# Display18_Cape.net
KiCad netlist of a schematic drawn in EAGLE
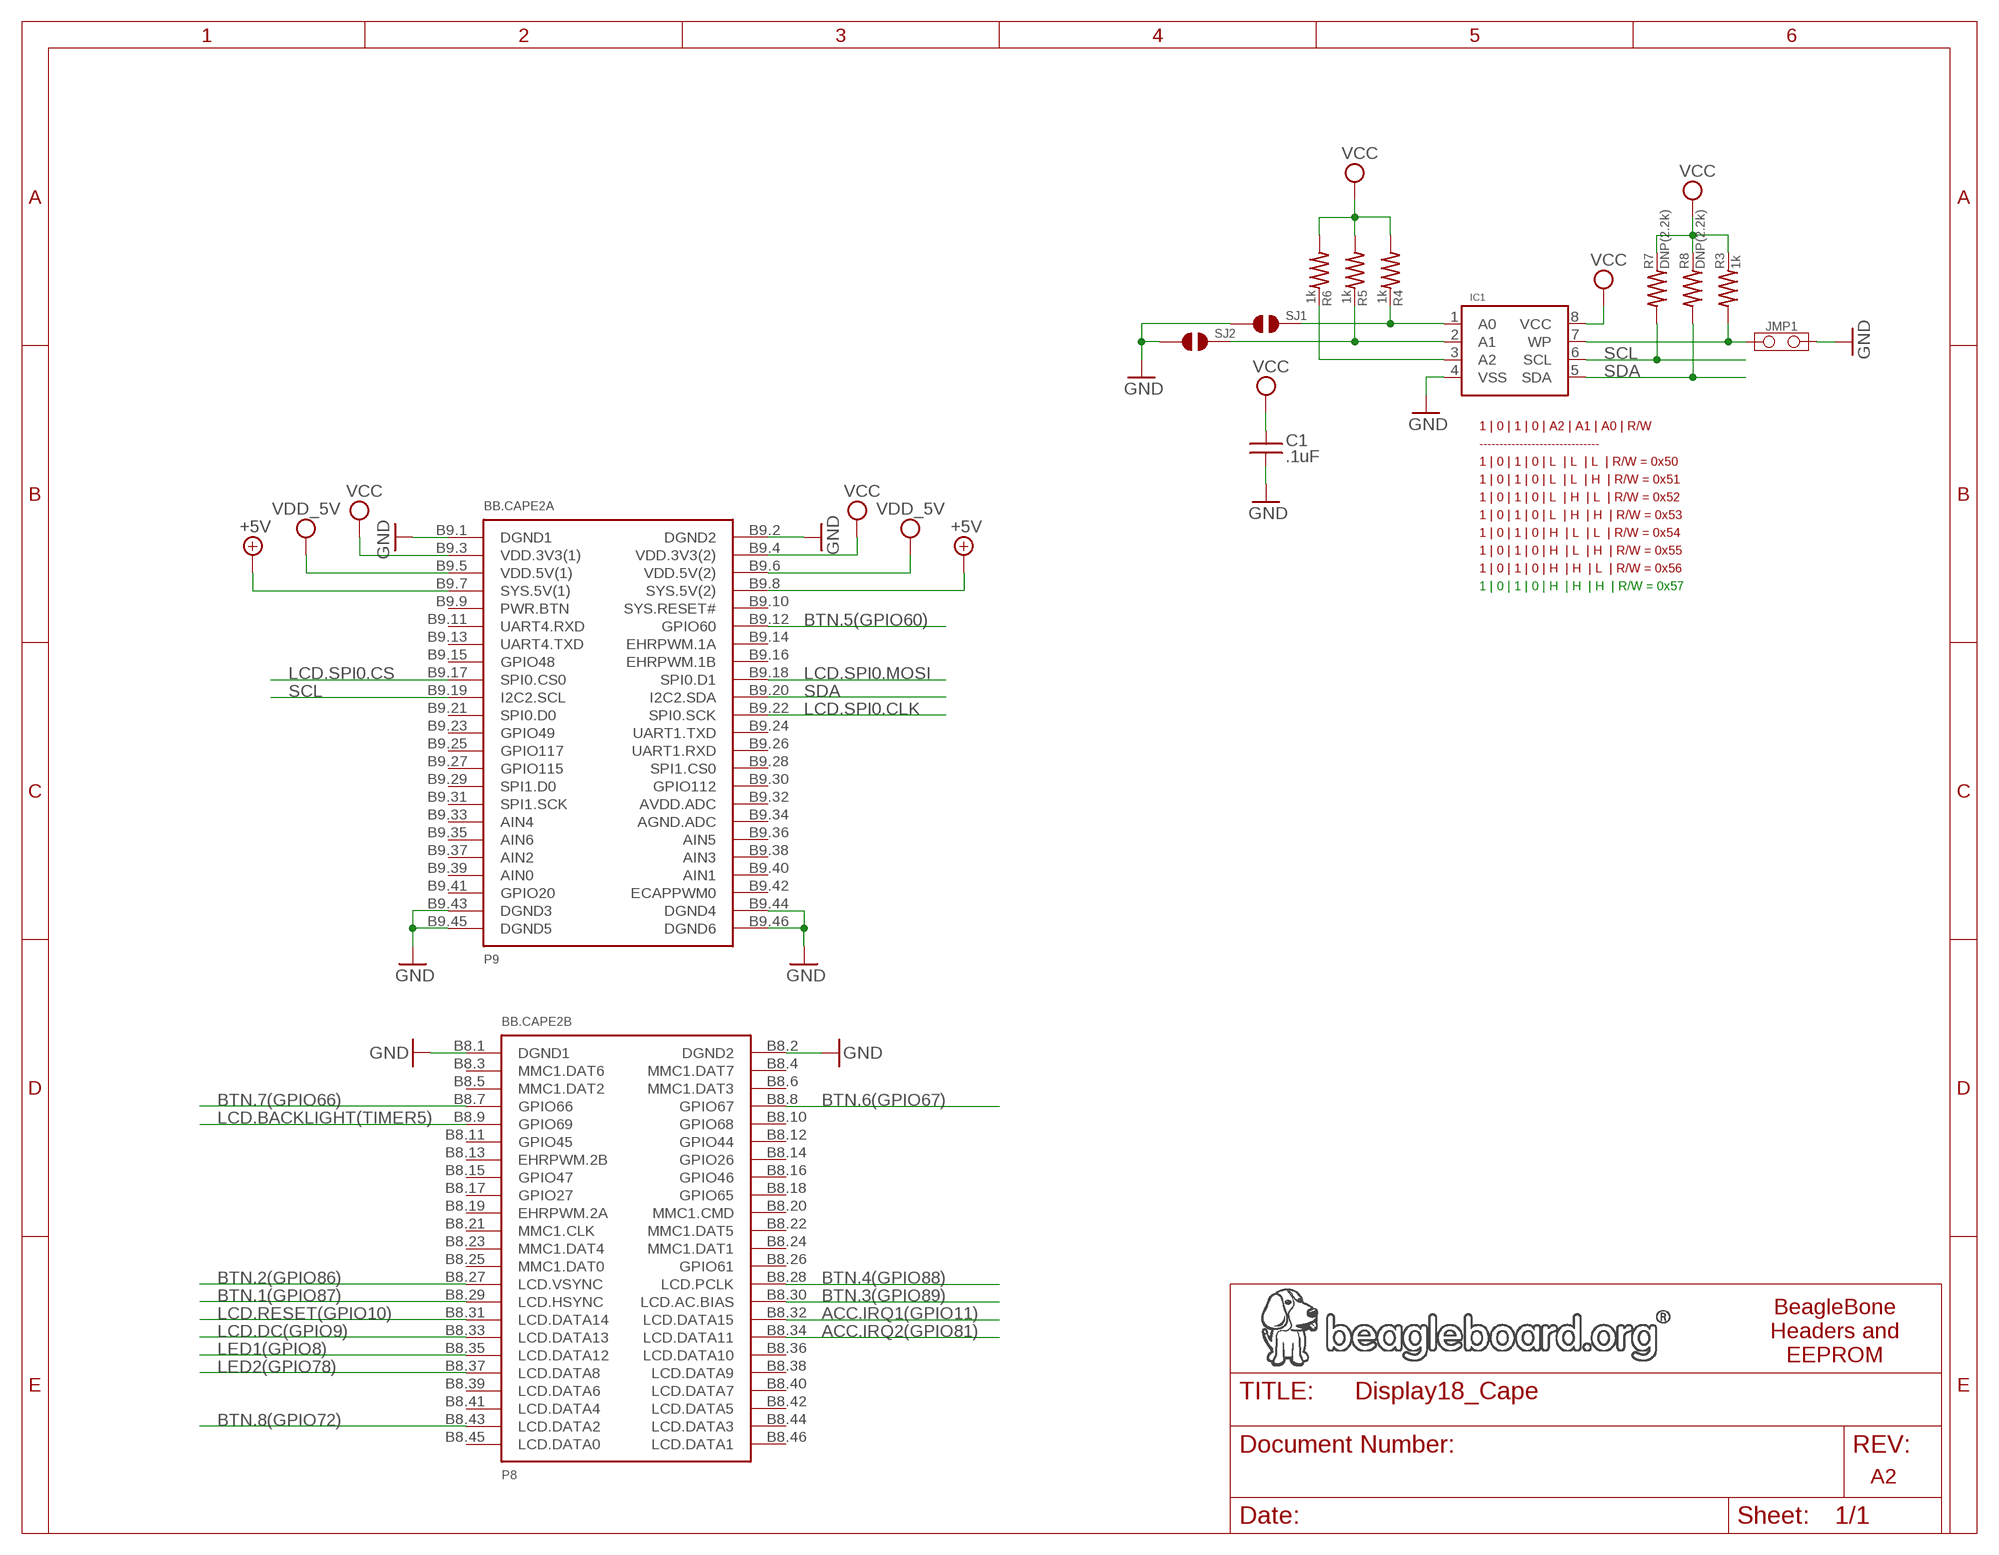
[diagram p0: schematic, sheet 1, part 1 of 2]
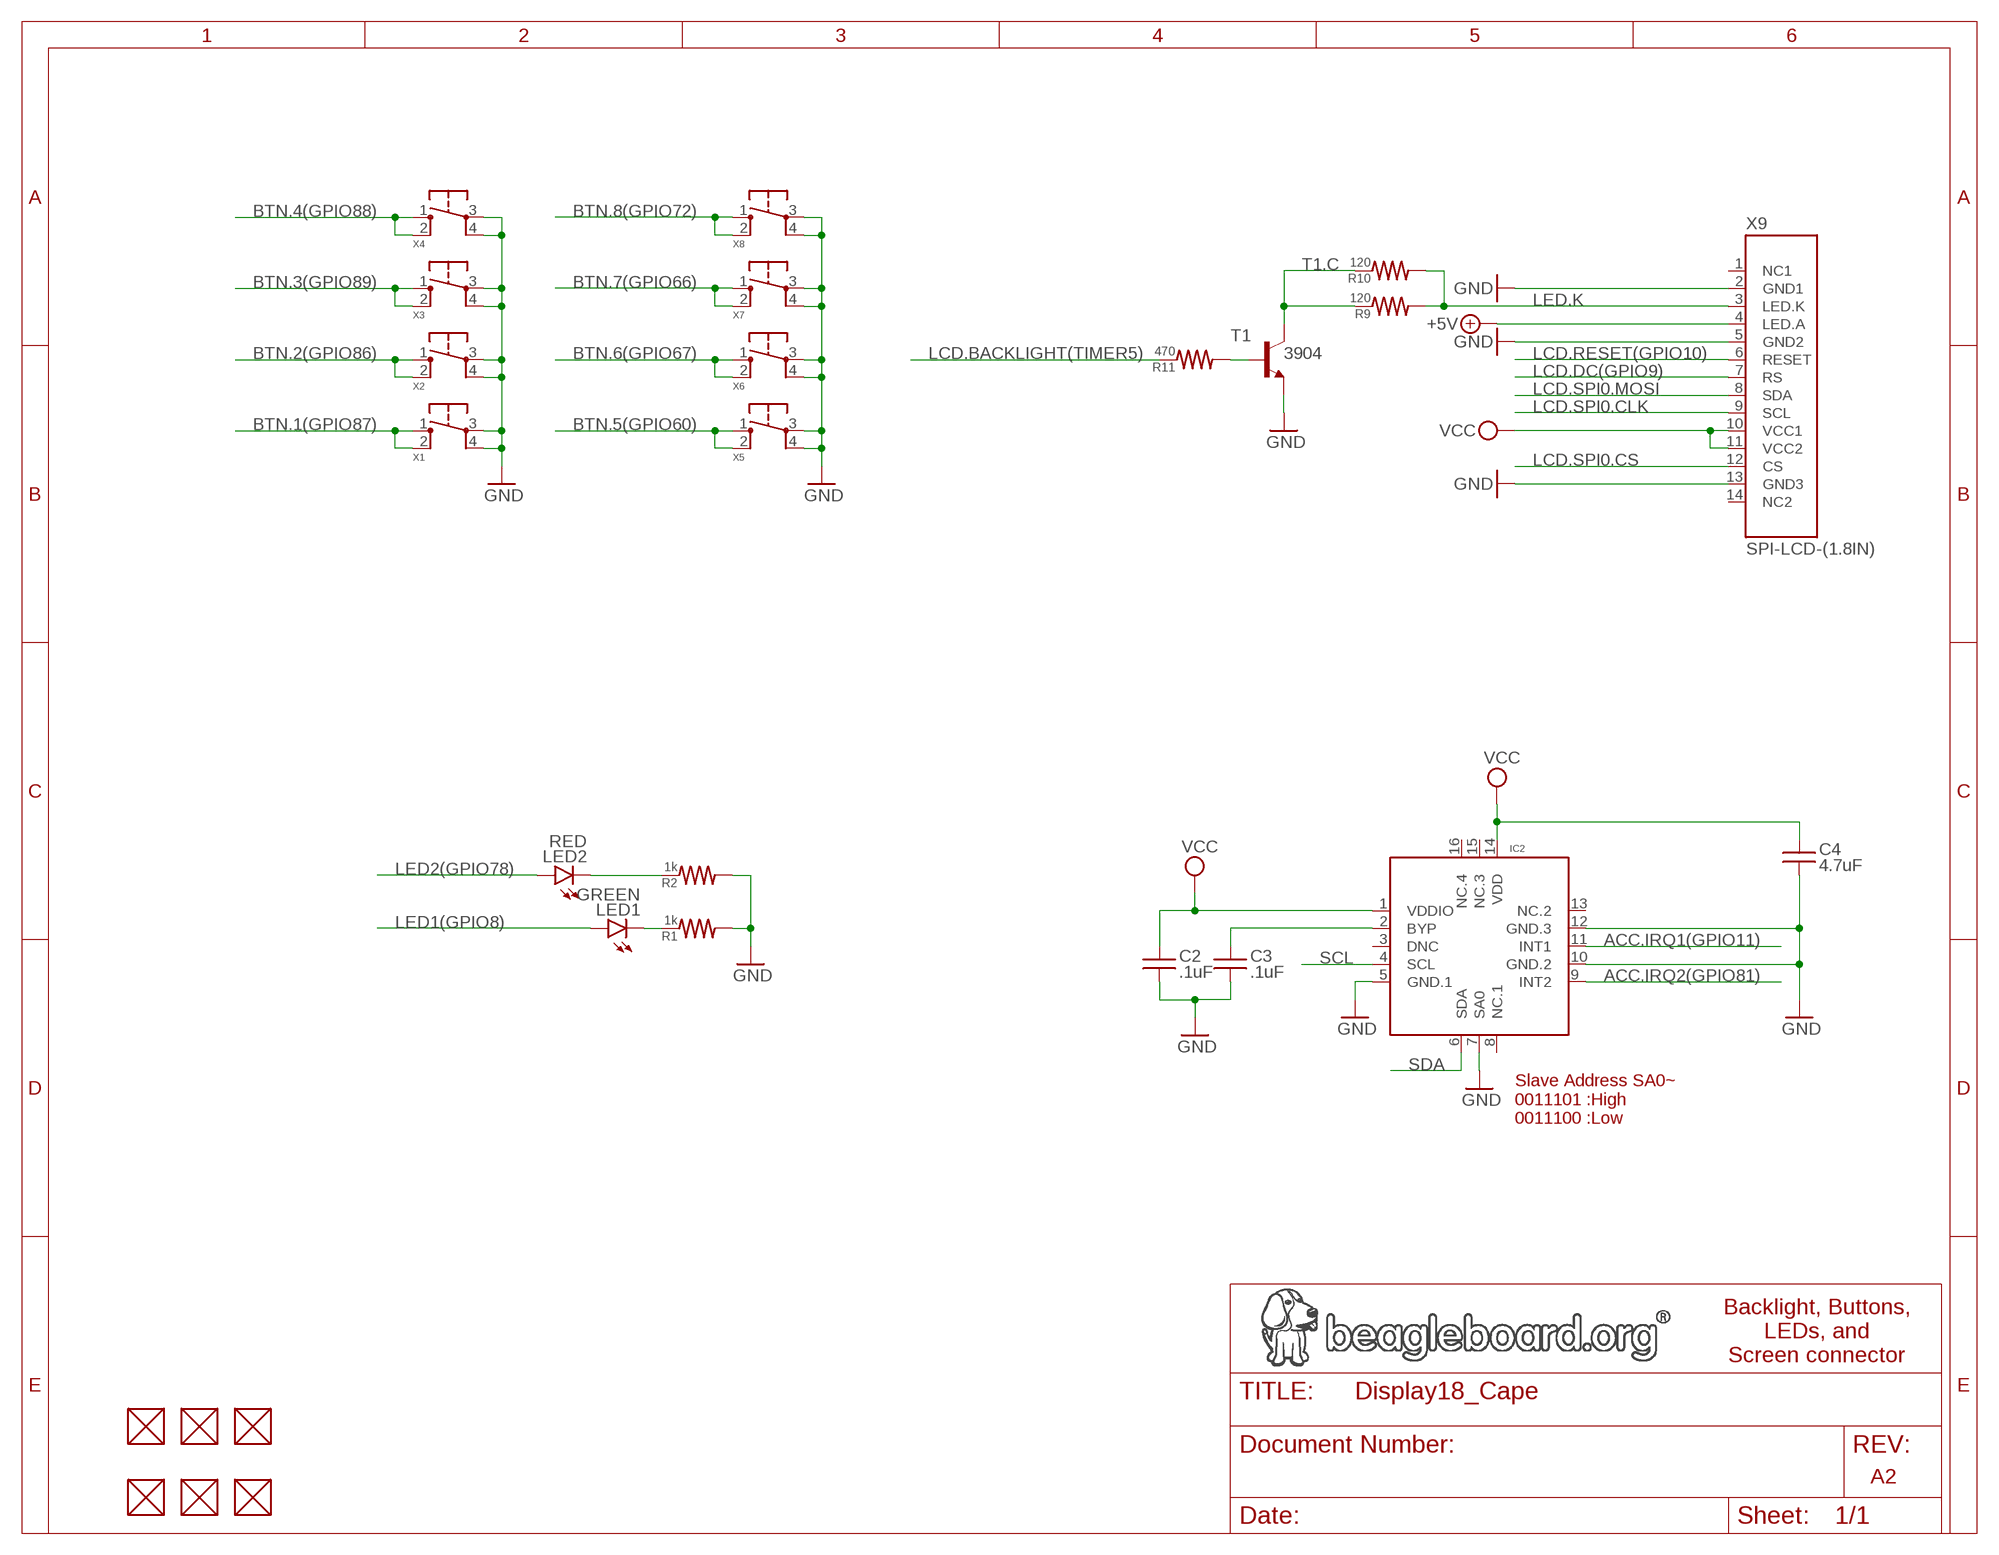
[diagram p1: schematic, sheet 1, part 2 of 2]

(export (version "E")
  (design (tool "Eeschema 10.0.6"))
  (components
    (comp (ref "BB.CAPE2")
      (value "BEAGLEBONE.CAPE.BOTTOM-ONLY-PADS")
      (footprint "eagle-import:BEAGLEBONE.CAPE.BOTTOM-ONLY-PADS")
      (libsource (lib "eagle-import") (part "BEAGLEBONE.CAPE.BOTTOM-ONLY-PADS"))
    )
    (comp (ref "C1")
      (value ".1uF")
      (footprint "eagle-import:0402")
      (libsource (lib "eagle-import") (part "CAPACITOR-(INCH)-0402"))
    )
    (comp (ref "C2")
      (value ".1uF")
      (footprint "eagle-import:0402")
      (libsource (lib "eagle-import") (part "CAPACITOR-(INCH)-0402"))
    )
    (comp (ref "C3")
      (value ".1uF")
      (footprint "eagle-import:0402")
      (libsource (lib "eagle-import") (part "CAPACITOR-(INCH)-0402"))
    )
    (comp (ref "C4")
      (value "4.7uF")
      (footprint "eagle-import:0603")
      (libsource (lib "eagle-import") (part "CAPACITOR-(INCH)-0603"))
    )
    (comp (ref "FUD1")
      (value "FIDUCIAL")
      (footprint "eagle-import:FIDUCIAL_40MIL")
      (libsource (lib "eagle-import") (part "FIDUCIAL"))
    )
    (comp (ref "FUD2")
      (value "FIDUCIAL")
      (footprint "eagle-import:FIDUCIAL_40MIL")
      (libsource (lib "eagle-import") (part "FIDUCIAL"))
    )
    (comp (ref "FUD3")
      (value "FIDUCIAL")
      (footprint "eagle-import:FIDUCIAL_40MIL")
      (libsource (lib "eagle-import") (part "FIDUCIAL"))
    )
    (comp (ref "FUD4")
      (value "FIDUCIAL")
      (footprint "eagle-import:FIDUCIAL_40MIL")
      (libsource (lib "eagle-import") (part "FIDUCIAL"))
    )
    (comp (ref "FUD5")
      (value "FIDUCIAL")
      (footprint "eagle-import:FIDUCIAL_40MIL")
      (libsource (lib "eagle-import") (part "FIDUCIAL"))
    )
    (comp (ref "FUD6")
      (value "FIDUCIAL")
      (footprint "eagle-import:FIDUCIAL_40MIL")
      (libsource (lib "eagle-import") (part "FIDUCIAL"))
    )
    (comp (ref "IC1")
      (value "CAT24C32")
      (footprint "eagle-import:UDFN8,2X3(ON-SEMI)")
      (libsource (lib "eagle-import") (part "CAT24C32"))
    )
    (comp (ref "IC2")
      (value "MMA8453Q")
      (footprint "eagle-import:QFN-16-(MMA8453Q)")
      (libsource (lib "eagle-import") (part "MMA8453Q"))
    )
    (comp (ref "JMP1")
      (value "JUMPER-(X2)")
      (footprint "eagle-import:JUMPER-(X2)")
      (libsource (lib "eagle-import") (part "JUMPER-(X2)"))
    )
    (comp (ref "LED1")
      (value "GREEN")
      (footprint "eagle-import:0805-LED")
      (libsource (lib "eagle-import") (part "LED-(INCH)-0805"))
    )
    (comp (ref "LED2")
      (value "RED")
      (footprint "eagle-import:0805-LED")
      (libsource (lib "eagle-import") (part "LED-(INCH)-0805"))
    )
    (comp (ref "R1")
      (value "1k")
      (footprint "eagle-import:0402")
      (libsource (lib "eagle-import") (part "RESISTOR-(INCH)-0402"))
    )
    (comp (ref "R2")
      (value "1k")
      (footprint "eagle-import:0402")
      (libsource (lib "eagle-import") (part "RESISTOR-(INCH)-0402"))
    )
    (comp (ref "R3")
      (value "1k")
      (footprint "eagle-import:0402")
      (libsource (lib "eagle-import") (part "RESISTOR-(INCH)-0402"))
    )
    (comp (ref "R4")
      (value "1k")
      (footprint "eagle-import:0402")
      (libsource (lib "eagle-import") (part "RESISTOR-(INCH)-0402"))
    )
    (comp (ref "R5")
      (value "1k")
      (footprint "eagle-import:0402")
      (libsource (lib "eagle-import") (part "RESISTOR-(INCH)-0402"))
    )
    (comp (ref "R6")
      (value "1k")
      (footprint "eagle-import:0402")
      (libsource (lib "eagle-import") (part "RESISTOR-(INCH)-0402"))
    )
    (comp (ref "R7")
      (value "DNP(2.2k)")
      (footprint "eagle-import:0402")
      (libsource (lib "eagle-import") (part "RESISTOR-(INCH)-0402"))
    )
    (comp (ref "R8")
      (value "DNP(2.2k)")
      (footprint "eagle-import:0402")
      (libsource (lib "eagle-import") (part "RESISTOR-(INCH)-0402"))
    )
    (comp (ref "R9")
      (value "120")
      (footprint "eagle-import:0603")
      (libsource (lib "eagle-import") (part "RESISTOR-(INCH)-0603"))
    )
    (comp (ref "R10")
      (value "120")
      (footprint "eagle-import:0603")
      (libsource (lib "eagle-import") (part "RESISTOR-(INCH)-0603"))
    )
    (comp (ref "R11")
      (value "470")
      (footprint "eagle-import:0603")
      (libsource (lib "eagle-import") (part "RESISTOR-(INCH)-0603"))
    )
    (comp (ref "SJ1")
      (value "SOLDER.JOINT-(INCH)-0402")
      (footprint "eagle-import:SOLDER.JOINT(0402)")
      (libsource (lib "eagle-import") (part "SOLDER.JOINT-(INCH)-0402"))
    )
    (comp (ref "SJ2")
      (value "SOLDER.JOINT-(INCH)-0402")
      (footprint "eagle-import:SOLDER.JOINT(0402)")
      (libsource (lib "eagle-import") (part "SOLDER.JOINT-(INCH)-0402"))
    )
    (comp (ref "T1")
      (value "3904")
      (footprint "eagle-import:SOT23-BEC")
      (libsource (lib "eagle-import") (part "-NPN-SOT23-BECBC847"))
    )
    (comp (ref "X1")
      (value "6MM_TACTILE_SWITCH")
      (footprint "eagle-import:6MM_TACTILE-SWITCH")
      (libsource (lib "eagle-import") (part "6MM_TACTILE_SWITCH"))
    )
    (comp (ref "X2")
      (value "6MM_TACTILE_SWITCH")
      (footprint "eagle-import:6MM_TACTILE-SWITCH")
      (libsource (lib "eagle-import") (part "6MM_TACTILE_SWITCH"))
    )
    (comp (ref "X3")
      (value "6MM_TACTILE_SWITCH")
      (footprint "eagle-import:6MM_TACTILE-SWITCH")
      (libsource (lib "eagle-import") (part "6MM_TACTILE_SWITCH"))
    )
    (comp (ref "X4")
      (value "6MM_TACTILE_SWITCH")
      (footprint "eagle-import:6MM_TACTILE-SWITCH")
      (libsource (lib "eagle-import") (part "6MM_TACTILE_SWITCH"))
    )
    (comp (ref "X5")
      (value "6MM_TACTILE_SWITCH")
      (footprint "eagle-import:6MM_TACTILE-SWITCH")
      (libsource (lib "eagle-import") (part "6MM_TACTILE_SWITCH"))
    )
    (comp (ref "X6")
      (value "6MM_TACTILE_SWITCH")
      (footprint "eagle-import:6MM_TACTILE-SWITCH")
      (libsource (lib "eagle-import") (part "6MM_TACTILE_SWITCH"))
    )
    (comp (ref "X7")
      (value "6MM_TACTILE_SWITCH")
      (footprint "eagle-import:6MM_TACTILE-SWITCH")
      (libsource (lib "eagle-import") (part "6MM_TACTILE_SWITCH"))
    )
    (comp (ref "X8")
      (value "6MM_TACTILE_SWITCH")
      (footprint "eagle-import:6MM_TACTILE-SWITCH")
      (libsource (lib "eagle-import") (part "6MM_TACTILE_SWITCH"))
    )
    (comp (ref "X9")
      (value "SPI-LCD-(1.8IN)")
      (footprint "eagle-import:LCD-(1.8IN)")
      (libsource (lib "eagle-import") (part "SPI-LCD-(1.8IN)"))
    )
  )
  (nets
    (net (code "1") (name "+5V") (class "Default")
      (node (ref "BB.CAPE2") (pin "B9.7") (pinfunction "SYS.5V(1)_B9.7") (pintype "bidirectional"))
      (node (ref "BB.CAPE2") (pin "B9.8") (pinfunction "SYS.5V(2)_B9.8") (pintype "bidirectional"))
      (node (ref "X9") (pin "4") (pinfunction "LED.A_4") (pintype "bidirectional"))
    )
    (net (code "2") (name "/ACC.IRQ1(GPIO11)") (class "Default")
      (node (ref "BB.CAPE2") (pin "B8.32") (pinfunction "LCD.DATA15_B8.32") (pintype "bidirectional"))
      (node (ref "IC2") (pin "11") (pinfunction "INT1_11") (pintype "bidirectional"))
    )
    (net (code "3") (name "/ACC.IRQ2(GPIO81)") (class "Default")
      (node (ref "BB.CAPE2") (pin "B8.34") (pinfunction "LCD.DATA11_B8.34") (pintype "bidirectional"))
      (node (ref "IC2") (pin "9") (pinfunction "INT2_9") (pintype "bidirectional"))
    )
    (net (code "4") (name "/BTN.1(GPIO87)") (class "Default")
      (node (ref "BB.CAPE2") (pin "B8.29") (pinfunction "LCD.HSYNC_B8.29") (pintype "bidirectional"))
      (node (ref "X1") (pin "1") (pinfunction "1_1") (pintype "bidirectional"))
      (node (ref "X1") (pin "2") (pinfunction "2_2") (pintype "bidirectional"))
    )
    (net (code "5") (name "/BTN.2(GPIO86)") (class "Default")
      (node (ref "BB.CAPE2") (pin "B8.27") (pinfunction "LCD.VSYNC_B8.27") (pintype "bidirectional"))
      (node (ref "X2") (pin "1") (pinfunction "1_1") (pintype "bidirectional"))
      (node (ref "X2") (pin "2") (pinfunction "2_2") (pintype "bidirectional"))
    )
    (net (code "6") (name "/BTN.3(GPIO89)") (class "Default")
      (node (ref "BB.CAPE2") (pin "B8.30") (pinfunction "LCD.AC.BIAS_B8.30") (pintype "bidirectional"))
      (node (ref "X3") (pin "1") (pinfunction "1_1") (pintype "bidirectional"))
      (node (ref "X3") (pin "2") (pinfunction "2_2") (pintype "bidirectional"))
    )
    (net (code "7") (name "/BTN.4(GPIO88)") (class "Default")
      (node (ref "BB.CAPE2") (pin "B8.28") (pinfunction "LCD.PCLK_B8.28") (pintype "bidirectional"))
      (node (ref "X4") (pin "1") (pinfunction "1_1") (pintype "bidirectional"))
      (node (ref "X4") (pin "2") (pinfunction "2_2") (pintype "bidirectional"))
    )
    (net (code "8") (name "/BTN.5(GPIO60)") (class "Default")
      (node (ref "BB.CAPE2") (pin "B9.12") (pinfunction "GPIO60_B9.12") (pintype "bidirectional"))
      (node (ref "X5") (pin "1") (pinfunction "1_1") (pintype "bidirectional"))
      (node (ref "X5") (pin "2") (pinfunction "2_2") (pintype "bidirectional"))
    )
    (net (code "9") (name "/BTN.6(GPIO67)") (class "Default")
      (node (ref "BB.CAPE2") (pin "B8.8") (pinfunction "GPIO67_B8.8") (pintype "bidirectional"))
      (node (ref "X6") (pin "1") (pinfunction "1_1") (pintype "bidirectional"))
      (node (ref "X6") (pin "2") (pinfunction "2_2") (pintype "bidirectional"))
    )
    (net (code "10") (name "/BTN.7(GPIO66)") (class "Default")
      (node (ref "BB.CAPE2") (pin "B8.7") (pinfunction "GPIO66_B8.7") (pintype "bidirectional"))
      (node (ref "X7") (pin "1") (pinfunction "1_1") (pintype "bidirectional"))
      (node (ref "X7") (pin "2") (pinfunction "2_2") (pintype "bidirectional"))
    )
    (net (code "11") (name "/BTN.8(GPIO72)") (class "Default")
      (node (ref "BB.CAPE2") (pin "B8.43") (pinfunction "LCD.DATA2_B8.43") (pintype "bidirectional"))
      (node (ref "X8") (pin "1") (pinfunction "1_1") (pintype "bidirectional"))
      (node (ref "X8") (pin "2") (pinfunction "2_2") (pintype "bidirectional"))
    )
    (net (code "12") (name "/LCD.BACKLIGHT(TIMER5)") (class "Default")
      (node (ref "BB.CAPE2") (pin "B8.9") (pinfunction "GPIO69_B8.9") (pintype "bidirectional"))
      (node (ref "R11") (pin "2") (pinfunction "2_2") (pintype "bidirectional"))
    )
    (net (code "13") (name "/LCD.DC(GPIO9)") (class "Default")
      (node (ref "BB.CAPE2") (pin "B8.33") (pinfunction "LCD.DATA13_B8.33") (pintype "bidirectional"))
      (node (ref "X9") (pin "7") (pinfunction "RS_7") (pintype "bidirectional"))
    )
    (net (code "14") (name "/LCD.RESET(GPIO10)") (class "Default")
      (node (ref "BB.CAPE2") (pin "B8.31") (pinfunction "LCD.DATA14_B8.31") (pintype "bidirectional"))
      (node (ref "X9") (pin "6") (pinfunction "RESET_6") (pintype "bidirectional"))
    )
    (net (code "15") (name "/LCD.SPI0.CLK") (class "Default")
      (node (ref "BB.CAPE2") (pin "B9.22") (pinfunction "SPI0.SCK_B9.22") (pintype "bidirectional"))
      (node (ref "X9") (pin "9") (pinfunction "SCL_9") (pintype "bidirectional"))
    )
    (net (code "16") (name "/LCD.SPI0.CS") (class "Default")
      (node (ref "BB.CAPE2") (pin "B9.17") (pinfunction "SPI0.CS0_B9.17") (pintype "bidirectional"))
      (node (ref "X9") (pin "12") (pinfunction "CS_12") (pintype "bidirectional"))
    )
    (net (code "17") (name "/LCD.SPI0.MOSI") (class "Default")
      (node (ref "BB.CAPE2") (pin "B9.18") (pinfunction "SPI0.D1_B9.18") (pintype "bidirectional"))
      (node (ref "X9") (pin "8") (pinfunction "SDA_8") (pintype "bidirectional"))
    )
    (net (code "18") (name "/LED.K") (class "Default")
      (node (ref "R10") (pin "1") (pinfunction "1_1") (pintype "bidirectional"))
      (node (ref "R9") (pin "1") (pinfunction "1_1") (pintype "bidirectional"))
      (node (ref "X9") (pin "3") (pinfunction "LED.K_3") (pintype "bidirectional"))
    )
    (net (code "19") (name "/LED1(GPIO8)") (class "Default")
      (node (ref "BB.CAPE2") (pin "B8.35") (pinfunction "LCD.DATA12_B8.35") (pintype "bidirectional"))
      (node (ref "LED1") (pin "A") (pinfunction "A_A") (pintype "passive"))
    )
    (net (code "20") (name "/LED2(GPIO78)") (class "Default")
      (node (ref "BB.CAPE2") (pin "B8.37") (pinfunction "LCD.DATA8_B8.37") (pintype "bidirectional"))
      (node (ref "LED2") (pin "A") (pinfunction "A_A") (pintype "passive"))
    )
    (net (code "21") (name "/SCL") (class "Default")
      (node (ref "BB.CAPE2") (pin "B9.19") (pinfunction "I2C2.SCL_B9.19") (pintype "bidirectional"))
      (node (ref "IC1") (pin "6") (pinfunction "SCL_6") (pintype "bidirectional"))
      (node (ref "IC2") (pin "4") (pinfunction "SCL_4") (pintype "bidirectional"))
      (node (ref "R7") (pin "1") (pinfunction "1_1") (pintype "bidirectional"))
    )
    (net (code "22") (name "/SDA") (class "Default")
      (node (ref "BB.CAPE2") (pin "B9.20") (pinfunction "I2C2.SDA_B9.20") (pintype "bidirectional"))
      (node (ref "IC1") (pin "5") (pinfunction "SDA_5") (pintype "bidirectional"))
      (node (ref "IC2") (pin "6") (pinfunction "SDA_6") (pintype "bidirectional"))
      (node (ref "R8") (pin "1") (pinfunction "1_1") (pintype "bidirectional"))
    )
    (net (code "23") (name "/T1.C") (class "Default")
      (node (ref "R10") (pin "2") (pinfunction "2_2") (pintype "bidirectional"))
      (node (ref "R9") (pin "2") (pinfunction "2_2") (pintype "bidirectional"))
      (node (ref "T1") (pin "C") (pinfunction "C_C") (pintype "passive"))
    )
    (net (code "24") (name "GND") (class "Default")
      (node (ref "BB.CAPE2") (pin "B8.1") (pinfunction "DGND1_B8.1") (pintype "bidirectional"))
      (node (ref "BB.CAPE2") (pin "B8.2") (pinfunction "DGND2_B8.2") (pintype "bidirectional"))
      (node (ref "BB.CAPE2") (pin "B9.1") (pinfunction "DGND1_B9.1") (pintype "bidirectional"))
      (node (ref "BB.CAPE2") (pin "B9.2") (pinfunction "DGND2_B9.2") (pintype "bidirectional"))
      (node (ref "BB.CAPE2") (pin "B9.43") (pinfunction "DGND3_B9.43") (pintype "bidirectional"))
      (node (ref "BB.CAPE2") (pin "B9.44") (pinfunction "DGND4_B9.44") (pintype "bidirectional"))
      (node (ref "BB.CAPE2") (pin "B9.45") (pinfunction "DGND5_B9.45") (pintype "bidirectional"))
      (node (ref "BB.CAPE2") (pin "B9.46") (pinfunction "DGND6_B9.46") (pintype "bidirectional"))
      (node (ref "C1") (pin "2") (pinfunction "2_2") (pintype "bidirectional"))
      (node (ref "C2") (pin "2") (pinfunction "2_2") (pintype "bidirectional"))
      (node (ref "C3") (pin "2") (pinfunction "2_2") (pintype "bidirectional"))
      (node (ref "C4") (pin "2") (pinfunction "2_2") (pintype "bidirectional"))
      (node (ref "IC1") (pin "4") (pinfunction "VSS_4") (pintype "bidirectional"))
      (node (ref "IC2") (pin "10") (pinfunction "GND.2_10") (pintype "bidirectional"))
      (node (ref "IC2") (pin "12") (pinfunction "GND.3_12") (pintype "bidirectional"))
      (node (ref "IC2") (pin "5") (pinfunction "GND.1_5") (pintype "bidirectional"))
      (node (ref "IC2") (pin "7") (pinfunction "SA0_7") (pintype "bidirectional"))
      (node (ref "JMP1") (pin "2") (pinfunction "2_2") (pintype "bidirectional"))
      (node (ref "R1") (pin "1") (pinfunction "1_1") (pintype "bidirectional"))
      (node (ref "R2") (pin "1") (pinfunction "1_1") (pintype "bidirectional"))
      (node (ref "SJ1") (pin "1") (pinfunction "1_1") (pintype "bidirectional"))
      (node (ref "SJ2") (pin "1") (pinfunction "1_1") (pintype "bidirectional"))
      (node (ref "T1") (pin "E") (pinfunction "E_E") (pintype "passive"))
      (node (ref "X1") (pin "3") (pinfunction "3_3") (pintype "bidirectional"))
      (node (ref "X1") (pin "4") (pinfunction "4_4") (pintype "bidirectional"))
      (node (ref "X2") (pin "3") (pinfunction "3_3") (pintype "bidirectional"))
      (node (ref "X2") (pin "4") (pinfunction "4_4") (pintype "bidirectional"))
      (node (ref "X3") (pin "3") (pinfunction "3_3") (pintype "bidirectional"))
      (node (ref "X3") (pin "4") (pinfunction "4_4") (pintype "bidirectional"))
      (node (ref "X4") (pin "3") (pinfunction "3_3") (pintype "bidirectional"))
      (node (ref "X4") (pin "4") (pinfunction "4_4") (pintype "bidirectional"))
      (node (ref "X5") (pin "3") (pinfunction "3_3") (pintype "bidirectional"))
      (node (ref "X5") (pin "4") (pinfunction "4_4") (pintype "bidirectional"))
      (node (ref "X6") (pin "3") (pinfunction "3_3") (pintype "bidirectional"))
      (node (ref "X6") (pin "4") (pinfunction "4_4") (pintype "bidirectional"))
      (node (ref "X7") (pin "3") (pinfunction "3_3") (pintype "bidirectional"))
      (node (ref "X7") (pin "4") (pinfunction "4_4") (pintype "bidirectional"))
      (node (ref "X8") (pin "3") (pinfunction "3_3") (pintype "bidirectional"))
      (node (ref "X8") (pin "4") (pinfunction "4_4") (pintype "bidirectional"))
      (node (ref "X9") (pin "13") (pinfunction "GND3_13") (pintype "bidirectional"))
      (node (ref "X9") (pin "2") (pinfunction "GND1_2") (pintype "bidirectional"))
      (node (ref "X9") (pin "5") (pinfunction "GND2_5") (pintype "bidirectional"))
    )
    (net (code "25") (name "Net-(IC1-A0)") (class "Default")
      (node (ref "IC1") (pin "1") (pinfunction "A0_1") (pintype "bidirectional"))
      (node (ref "R4") (pin "2") (pinfunction "2_2") (pintype "bidirectional"))
      (node (ref "SJ1") (pin "2") (pinfunction "2_2") (pintype "bidirectional"))
    )
    (net (code "26") (name "Net-(IC1-A1)") (class "Default")
      (node (ref "IC1") (pin "2") (pinfunction "A1_2") (pintype "bidirectional"))
      (node (ref "R5") (pin "2") (pinfunction "2_2") (pintype "bidirectional"))
      (node (ref "SJ2") (pin "2") (pinfunction "2_2") (pintype "bidirectional"))
    )
    (net (code "27") (name "Net-(IC1-A2)") (class "Default")
      (node (ref "IC1") (pin "3") (pinfunction "A2_3") (pintype "bidirectional"))
      (node (ref "R6") (pin "2") (pinfunction "2_2") (pintype "bidirectional"))
    )
    (net (code "28") (name "Net-(IC1-WP)") (class "Default")
      (node (ref "IC1") (pin "7") (pinfunction "WP_7") (pintype "bidirectional"))
      (node (ref "JMP1") (pin "1") (pinfunction "1_1") (pintype "bidirectional"))
      (node (ref "R3") (pin "1") (pinfunction "1_1") (pintype "bidirectional"))
    )
    (net (code "29") (name "Net-(IC2-BYP)") (class "Default")
      (node (ref "C3") (pin "1") (pinfunction "1_1") (pintype "bidirectional"))
      (node (ref "IC2") (pin "2") (pinfunction "BYP_2") (pintype "bidirectional"))
    )
    (net (code "30") (name "Net-(LED1-PadK)") (class "Default")
      (node (ref "LED1") (pin "K") (pinfunction "K_K") (pintype "passive"))
      (node (ref "R1") (pin "2") (pinfunction "2_2") (pintype "bidirectional"))
    )
    (net (code "31") (name "Net-(LED2-PadK)") (class "Default")
      (node (ref "LED2") (pin "K") (pinfunction "K_K") (pintype "passive"))
      (node (ref "R2") (pin "2") (pinfunction "2_2") (pintype "bidirectional"))
    )
    (net (code "32") (name "Net-(R11-Pad1)") (class "Default")
      (node (ref "R11") (pin "1") (pinfunction "1_1") (pintype "bidirectional"))
      (node (ref "T1") (pin "B") (pinfunction "B_B") (pintype "passive"))
    )
    (net (code "33") (name "VCC") (class "Default")
      (node (ref "BB.CAPE2") (pin "B9.3") (pinfunction "VDD.3V3(1)_B9.3") (pintype "bidirectional"))
      (node (ref "BB.CAPE2") (pin "B9.4") (pinfunction "VDD.3V3(2)_B9.4") (pintype "bidirectional"))
      (node (ref "C1") (pin "1") (pinfunction "1_1") (pintype "bidirectional"))
      (node (ref "C2") (pin "1") (pinfunction "1_1") (pintype "bidirectional"))
      (node (ref "C4") (pin "1") (pinfunction "1_1") (pintype "bidirectional"))
      (node (ref "IC1") (pin "8") (pinfunction "VCC_8") (pintype "bidirectional"))
      (node (ref "IC2") (pin "1") (pinfunction "VDDIO_1") (pintype "bidirectional"))
      (node (ref "IC2") (pin "14") (pinfunction "VDD_14") (pintype "bidirectional"))
      (node (ref "R3") (pin "2") (pinfunction "2_2") (pintype "bidirectional"))
      (node (ref "R4") (pin "1") (pinfunction "1_1") (pintype "bidirectional"))
      (node (ref "R5") (pin "1") (pinfunction "1_1") (pintype "bidirectional"))
      (node (ref "R6") (pin "1") (pinfunction "1_1") (pintype "bidirectional"))
      (node (ref "R7") (pin "2") (pinfunction "2_2") (pintype "bidirectional"))
      (node (ref "R8") (pin "2") (pinfunction "2_2") (pintype "bidirectional"))
      (node (ref "X9") (pin "10") (pinfunction "VCC1_10") (pintype "bidirectional"))
      (node (ref "X9") (pin "11") (pinfunction "VCC2_11") (pintype "bidirectional"))
    )
    (net (code "34") (name "VDD_5V") (class "Default")
      (node (ref "BB.CAPE2") (pin "B9.5") (pinfunction "VDD.5V(1)_B9.5") (pintype "bidirectional"))
      (node (ref "BB.CAPE2") (pin "B9.6") (pinfunction "VDD.5V(2)_B9.6") (pintype "bidirectional"))
    )
    (net (code "35") (name "unconnected-(BB.CAPE2A-AGND.ADC-PadB9.34)") (class "Default")
      (node (ref "BB.CAPE2") (pin "B9.34") (pinfunction "AGND.ADC_B9.34") (pintype "bidirectional"))
    )
    (net (code "36") (name "unconnected-(BB.CAPE2A-AIN0-PadB9.39)") (class "Default")
      (node (ref "BB.CAPE2") (pin "B9.39") (pinfunction "AIN0_B9.39") (pintype "bidirectional"))
    )
    (net (code "37") (name "unconnected-(BB.CAPE2A-AIN1-PadB9.40)") (class "Default")
      (node (ref "BB.CAPE2") (pin "B9.40") (pinfunction "AIN1_B9.40") (pintype "bidirectional"))
    )
    (net (code "38") (name "unconnected-(BB.CAPE2A-AIN2-PadB9.37)") (class "Default")
      (node (ref "BB.CAPE2") (pin "B9.37") (pinfunction "AIN2_B9.37") (pintype "bidirectional"))
    )
    (net (code "39") (name "unconnected-(BB.CAPE2A-AIN3-PadB9.38)") (class "Default")
      (node (ref "BB.CAPE2") (pin "B9.38") (pinfunction "AIN3_B9.38") (pintype "bidirectional"))
    )
    (net (code "40") (name "unconnected-(BB.CAPE2A-AIN4-PadB9.33)") (class "Default")
      (node (ref "BB.CAPE2") (pin "B9.33") (pinfunction "AIN4_B9.33") (pintype "bidirectional"))
    )
    (net (code "41") (name "unconnected-(BB.CAPE2A-AIN5-PadB9.36)") (class "Default")
      (node (ref "BB.CAPE2") (pin "B9.36") (pinfunction "AIN5_B9.36") (pintype "bidirectional"))
    )
    (net (code "42") (name "unconnected-(BB.CAPE2A-AIN6-PadB9.35)") (class "Default")
      (node (ref "BB.CAPE2") (pin "B9.35") (pinfunction "AIN6_B9.35") (pintype "bidirectional"))
    )
    (net (code "43") (name "unconnected-(BB.CAPE2A-AVDD.ADC-PadB9.32)") (class "Default")
      (node (ref "BB.CAPE2") (pin "B9.32") (pinfunction "AVDD.ADC_B9.32") (pintype "bidirectional"))
    )
    (net (code "44") (name "unconnected-(BB.CAPE2A-ECAPPWM0-PadB9.42)") (class "Default")
      (node (ref "BB.CAPE2") (pin "B9.42") (pinfunction "ECAPPWM0_B9.42") (pintype "bidirectional"))
    )
    (net (code "45") (name "unconnected-(BB.CAPE2A-EHRPWM.1A-PadB9.14)") (class "Default")
      (node (ref "BB.CAPE2") (pin "B9.14") (pinfunction "EHRPWM.1A_B9.14") (pintype "bidirectional"))
    )
    (net (code "46") (name "unconnected-(BB.CAPE2A-EHRPWM.1B-PadB9.16)") (class "Default")
      (node (ref "BB.CAPE2") (pin "B9.16") (pinfunction "EHRPWM.1B_B9.16") (pintype "bidirectional"))
    )
    (net (code "47") (name "unconnected-(BB.CAPE2A-GPIO20-PadB9.41)") (class "Default")
      (node (ref "BB.CAPE2") (pin "B9.41") (pinfunction "GPIO20_B9.41") (pintype "bidirectional"))
    )
    (net (code "48") (name "unconnected-(BB.CAPE2A-GPIO48-PadB9.15)") (class "Default")
      (node (ref "BB.CAPE2") (pin "B9.15") (pinfunction "GPIO48_B9.15") (pintype "bidirectional"))
    )
    (net (code "49") (name "unconnected-(BB.CAPE2A-GPIO49-PadB9.23)") (class "Default")
      (node (ref "BB.CAPE2") (pin "B9.23") (pinfunction "GPIO49_B9.23") (pintype "bidirectional"))
    )
    (net (code "50") (name "unconnected-(BB.CAPE2A-GPIO112-PadB9.30)") (class "Default")
      (node (ref "BB.CAPE2") (pin "B9.30") (pinfunction "GPIO112_B9.30") (pintype "bidirectional"))
    )
    (net (code "51") (name "unconnected-(BB.CAPE2A-GPIO115-PadB9.27)") (class "Default")
      (node (ref "BB.CAPE2") (pin "B9.27") (pinfunction "GPIO115_B9.27") (pintype "bidirectional"))
    )
    (net (code "52") (name "unconnected-(BB.CAPE2A-GPIO117-PadB9.25)") (class "Default")
      (node (ref "BB.CAPE2") (pin "B9.25") (pinfunction "GPIO117_B9.25") (pintype "bidirectional"))
    )
    (net (code "53") (name "unconnected-(BB.CAPE2A-PWR.BTN-PadB9.9)") (class "Default")
      (node (ref "BB.CAPE2") (pin "B9.9") (pinfunction "PWR.BTN_B9.9") (pintype "bidirectional"))
    )
    (net (code "54") (name "unconnected-(BB.CAPE2A-SPI0.D0-PadB9.21)") (class "Default")
      (node (ref "BB.CAPE2") (pin "B9.21") (pinfunction "SPI0.D0_B9.21") (pintype "bidirectional"))
    )
    (net (code "55") (name "unconnected-(BB.CAPE2A-SPI1.CS0-PadB9.28)") (class "Default")
      (node (ref "BB.CAPE2") (pin "B9.28") (pinfunction "SPI1.CS0_B9.28") (pintype "bidirectional"))
    )
    (net (code "56") (name "unconnected-(BB.CAPE2A-SPI1.D0-PadB9.29)") (class "Default")
      (node (ref "BB.CAPE2") (pin "B9.29") (pinfunction "SPI1.D0_B9.29") (pintype "bidirectional"))
    )
    (net (code "57") (name "unconnected-(BB.CAPE2A-SPI1.SCK-PadB9.31)") (class "Default")
      (node (ref "BB.CAPE2") (pin "B9.31") (pinfunction "SPI1.SCK_B9.31") (pintype "bidirectional"))
    )
    (net (code "58") (name "unconnected-(BB.CAPE2A-SYS.RESET#-PadB9.10)") (class "Default")
      (node (ref "BB.CAPE2") (pin "B9.10") (pinfunction "SYS.RESET#_B9.10") (pintype "bidirectional"))
    )
    (net (code "59") (name "unconnected-(BB.CAPE2A-UART1.RXD-PadB9.26)") (class "Default")
      (node (ref "BB.CAPE2") (pin "B9.26") (pinfunction "UART1.RXD_B9.26") (pintype "bidirectional"))
    )
    (net (code "60") (name "unconnected-(BB.CAPE2A-UART1.TXD-PadB9.24)") (class "Default")
      (node (ref "BB.CAPE2") (pin "B9.24") (pinfunction "UART1.TXD_B9.24") (pintype "bidirectional"))
    )
    (net (code "61") (name "unconnected-(BB.CAPE2A-UART4.RXD-PadB9.11)") (class "Default")
      (node (ref "BB.CAPE2") (pin "B9.11") (pinfunction "UART4.RXD_B9.11") (pintype "bidirectional"))
    )
    (net (code "62") (name "unconnected-(BB.CAPE2A-UART4.TXD-PadB9.13)") (class "Default")
      (node (ref "BB.CAPE2") (pin "B9.13") (pinfunction "UART4.TXD_B9.13") (pintype "bidirectional"))
    )
    (net (code "63") (name "unconnected-(BB.CAPE2B-EHRPWM.2A-PadB8.19)") (class "Default")
      (node (ref "BB.CAPE2") (pin "B8.19") (pinfunction "EHRPWM.2A_B8.19") (pintype "bidirectional"))
    )
    (net (code "64") (name "unconnected-(BB.CAPE2B-EHRPWM.2B-PadB8.13)") (class "Default")
      (node (ref "BB.CAPE2") (pin "B8.13") (pinfunction "EHRPWM.2B_B8.13") (pintype "bidirectional"))
    )
    (net (code "65") (name "unconnected-(BB.CAPE2B-GPIO26-PadB8.14)") (class "Default")
      (node (ref "BB.CAPE2") (pin "B8.14") (pinfunction "GPIO26_B8.14") (pintype "bidirectional"))
    )
    (net (code "66") (name "unconnected-(BB.CAPE2B-GPIO27-PadB8.17)") (class "Default")
      (node (ref "BB.CAPE2") (pin "B8.17") (pinfunction "GPIO27_B8.17") (pintype "bidirectional"))
    )
    (net (code "67") (name "unconnected-(BB.CAPE2B-GPIO44-PadB8.12)") (class "Default")
      (node (ref "BB.CAPE2") (pin "B8.12") (pinfunction "GPIO44_B8.12") (pintype "bidirectional"))
    )
    (net (code "68") (name "unconnected-(BB.CAPE2B-GPIO45-PadB8.11)") (class "Default")
      (node (ref "BB.CAPE2") (pin "B8.11") (pinfunction "GPIO45_B8.11") (pintype "bidirectional"))
    )
    (net (code "69") (name "unconnected-(BB.CAPE2B-GPIO46-PadB8.16)") (class "Default")
      (node (ref "BB.CAPE2") (pin "B8.16") (pinfunction "GPIO46_B8.16") (pintype "bidirectional"))
    )
    (net (code "70") (name "unconnected-(BB.CAPE2B-GPIO47-PadB8.15)") (class "Default")
      (node (ref "BB.CAPE2") (pin "B8.15") (pinfunction "GPIO47_B8.15") (pintype "bidirectional"))
    )
    (net (code "71") (name "unconnected-(BB.CAPE2B-GPIO61-PadB8.26)") (class "Default")
      (node (ref "BB.CAPE2") (pin "B8.26") (pinfunction "GPIO61_B8.26") (pintype "bidirectional"))
    )
    (net (code "72") (name "unconnected-(BB.CAPE2B-GPIO65-PadB8.18)") (class "Default")
      (node (ref "BB.CAPE2") (pin "B8.18") (pinfunction "GPIO65_B8.18") (pintype "bidirectional"))
    )
    (net (code "73") (name "unconnected-(BB.CAPE2B-GPIO68-PadB8.10)") (class "Default")
      (node (ref "BB.CAPE2") (pin "B8.10") (pinfunction "GPIO68_B8.10") (pintype "bidirectional"))
    )
    (net (code "74") (name "unconnected-(BB.CAPE2B-LCD.DATA0-PadB8.45)") (class "Default")
      (node (ref "BB.CAPE2") (pin "B8.45") (pinfunction "LCD.DATA0_B8.45") (pintype "bidirectional"))
    )
    (net (code "75") (name "unconnected-(BB.CAPE2B-LCD.DATA1-PadB8.46)") (class "Default")
      (node (ref "BB.CAPE2") (pin "B8.46") (pinfunction "LCD.DATA1_B8.46") (pintype "bidirectional"))
    )
    (net (code "76") (name "unconnected-(BB.CAPE2B-LCD.DATA3-PadB8.44)") (class "Default")
      (node (ref "BB.CAPE2") (pin "B8.44") (pinfunction "LCD.DATA3_B8.44") (pintype "bidirectional"))
    )
    (net (code "77") (name "unconnected-(BB.CAPE2B-LCD.DATA4-PadB8.41)") (class "Default")
      (node (ref "BB.CAPE2") (pin "B8.41") (pinfunction "LCD.DATA4_B8.41") (pintype "bidirectional"))
    )
    (net (code "78") (name "unconnected-(BB.CAPE2B-LCD.DATA5-PadB8.42)") (class "Default")
      (node (ref "BB.CAPE2") (pin "B8.42") (pinfunction "LCD.DATA5_B8.42") (pintype "bidirectional"))
    )
    (net (code "79") (name "unconnected-(BB.CAPE2B-LCD.DATA6-PadB8.39)") (class "Default")
      (node (ref "BB.CAPE2") (pin "B8.39") (pinfunction "LCD.DATA6_B8.39") (pintype "bidirectional"))
    )
    (net (code "80") (name "unconnected-(BB.CAPE2B-LCD.DATA7-PadB8.40)") (class "Default")
      (node (ref "BB.CAPE2") (pin "B8.40") (pinfunction "LCD.DATA7_B8.40") (pintype "bidirectional"))
    )
    (net (code "81") (name "unconnected-(BB.CAPE2B-LCD.DATA9-PadB8.38)") (class "Default")
      (node (ref "BB.CAPE2") (pin "B8.38") (pinfunction "LCD.DATA9_B8.38") (pintype "bidirectional"))
    )
    (net (code "82") (name "unconnected-(BB.CAPE2B-LCD.DATA10-PadB8.36)") (class "Default")
      (node (ref "BB.CAPE2") (pin "B8.36") (pinfunction "LCD.DATA10_B8.36") (pintype "bidirectional"))
    )
    (net (code "83") (name "unconnected-(BB.CAPE2B-MMC1.CLK-PadB8.21)") (class "Default")
      (node (ref "BB.CAPE2") (pin "B8.21") (pinfunction "MMC1.CLK_B8.21") (pintype "bidirectional"))
    )
    (net (code "84") (name "unconnected-(BB.CAPE2B-MMC1.CMD-PadB8.20)") (class "Default")
      (node (ref "BB.CAPE2") (pin "B8.20") (pinfunction "MMC1.CMD_B8.20") (pintype "bidirectional"))
    )
    (net (code "85") (name "unconnected-(BB.CAPE2B-MMC1.DAT0-PadB8.25)") (class "Default")
      (node (ref "BB.CAPE2") (pin "B8.25") (pinfunction "MMC1.DAT0_B8.25") (pintype "bidirectional"))
    )
    (net (code "86") (name "unconnected-(BB.CAPE2B-MMC1.DAT1-PadB8.24)") (class "Default")
      (node (ref "BB.CAPE2") (pin "B8.24") (pinfunction "MMC1.DAT1_B8.24") (pintype "bidirectional"))
    )
    (net (code "87") (name "unconnected-(BB.CAPE2B-MMC1.DAT2-PadB8.5)") (class "Default")
      (node (ref "BB.CAPE2") (pin "B8.5") (pinfunction "MMC1.DAT2_B8.5") (pintype "bidirectional"))
    )
    (net (code "88") (name "unconnected-(BB.CAPE2B-MMC1.DAT3-PadB8.6)") (class "Default")
      (node (ref "BB.CAPE2") (pin "B8.6") (pinfunction "MMC1.DAT3_B8.6") (pintype "bidirectional"))
    )
    (net (code "89") (name "unconnected-(BB.CAPE2B-MMC1.DAT4-PadB8.23)") (class "Default")
      (node (ref "BB.CAPE2") (pin "B8.23") (pinfunction "MMC1.DAT4_B8.23") (pintype "bidirectional"))
    )
    (net (code "90") (name "unconnected-(BB.CAPE2B-MMC1.DAT5-PadB8.22)") (class "Default")
      (node (ref "BB.CAPE2") (pin "B8.22") (pinfunction "MMC1.DAT5_B8.22") (pintype "bidirectional"))
    )
    (net (code "91") (name "unconnected-(BB.CAPE2B-MMC1.DAT6-PadB8.3)") (class "Default")
      (node (ref "BB.CAPE2") (pin "B8.3") (pinfunction "MMC1.DAT6_B8.3") (pintype "bidirectional"))
    )
    (net (code "92") (name "unconnected-(BB.CAPE2B-MMC1.DAT7-PadB8.4)") (class "Default")
      (node (ref "BB.CAPE2") (pin "B8.4") (pinfunction "MMC1.DAT7_B8.4") (pintype "bidirectional"))
    )
    (net (code "93") (name "unconnected-(FUD1-PadP$1)") (class "Default")
      (node (ref "FUD1") (pin "P$1") (pinfunction "P$1_P$1") (pintype "no_connect"))
    )
    (net (code "94") (name "unconnected-(FUD2-PadP$1)") (class "Default")
      (node (ref "FUD2") (pin "P$1") (pinfunction "P$1_P$1") (pintype "no_connect"))
    )
    (net (code "95") (name "unconnected-(FUD3-PadP$1)") (class "Default")
      (node (ref "FUD3") (pin "P$1") (pinfunction "P$1_P$1") (pintype "no_connect"))
    )
    (net (code "96") (name "unconnected-(FUD4-PadP$1)") (class "Default")
      (node (ref "FUD4") (pin "P$1") (pinfunction "P$1_P$1") (pintype "no_connect"))
    )
    (net (code "97") (name "unconnected-(FUD5-PadP$1)") (class "Default")
      (node (ref "FUD5") (pin "P$1") (pinfunction "P$1_P$1") (pintype "no_connect"))
    )
    (net (code "98") (name "unconnected-(FUD6-PadP$1)") (class "Default")
      (node (ref "FUD6") (pin "P$1") (pinfunction "P$1_P$1") (pintype "no_connect"))
    )
    (net (code "99") (name "unconnected-(IC2-DNC-Pad3)") (class "Default")
      (node (ref "IC2") (pin "3") (pinfunction "DNC_3") (pintype "bidirectional"))
    )
    (net (code "100") (name "unconnected-(IC2-NC.1-Pad8)") (class "Default")
      (node (ref "IC2") (pin "8") (pinfunction "NC.1_8") (pintype "bidirectional"))
    )
    (net (code "101") (name "unconnected-(IC2-NC.2-Pad13)") (class "Default")
      (node (ref "IC2") (pin "13") (pinfunction "NC.2_13") (pintype "bidirectional"))
    )
    (net (code "102") (name "unconnected-(IC2-NC.3-Pad15)") (class "Default")
      (node (ref "IC2") (pin "15") (pinfunction "NC.3_15") (pintype "bidirectional"))
    )
    (net (code "103") (name "unconnected-(IC2-NC.4-Pad16)") (class "Default")
      (node (ref "IC2") (pin "16") (pinfunction "NC.4_16") (pintype "bidirectional"))
    )
    (net (code "104") (name "unconnected-(X9-NC1-Pad1)") (class "Default")
      (node (ref "X9") (pin "1") (pinfunction "NC1_1") (pintype "bidirectional"))
    )
    (net (code "105") (name "unconnected-(X9-NC2-Pad14)") (class "Default")
      (node (ref "X9") (pin "14") (pinfunction "NC2_14") (pintype "bidirectional"))
    )
  )
)
